# AMU-S02-V00-PSU3V3.net
KiCad netlist of a schematic drawn in Altium Designer
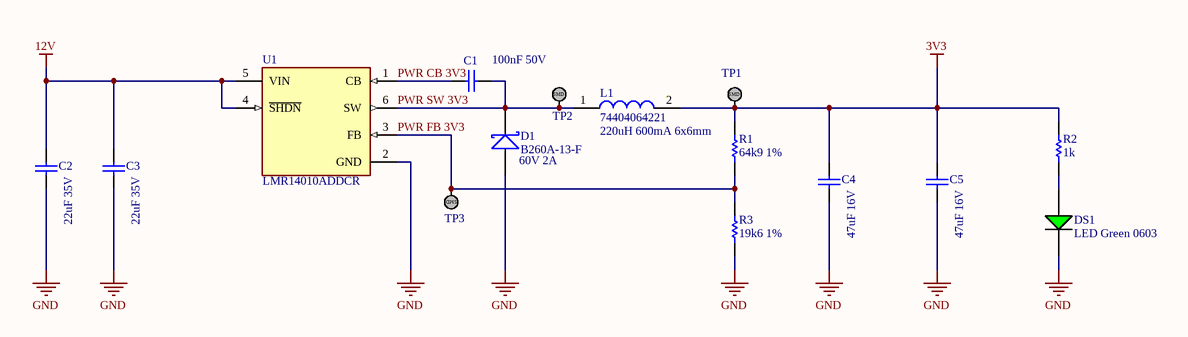
[diagram p0: AMU-S02-V00-PSU3V3.SchDoc]

(export (version "E")
  (design (tool "Eeschema 10.0.6"))
  (components
    (comp (ref "C1")
      (value "100nF 50V")
      (footprint "Cap_Ceramic_0603")
      (description "Capacitor, Ceramic, SMD, 100nF, 50V, 5%, X7R, 0603")
      (libsource (lib "StandardCapacitors") (part "100nF 50V 5% X7R 0603"))
    )
    (comp (ref "C2")
      (value "22uF 35V")
      (footprint "Cap_Ceramic_1206")
      (description "22µF ±20% 35V Ceramic Capacitor X5R 1206 (3216 Metric)")
      (libsource (lib "StandardCapacitors") (part "22uF 35V 20% X5R 1206"))
    )
    (comp (ref "C3")
      (value "22uF 35V")
      (footprint "Cap_Ceramic_1206")
      (description "22µF ±20% 35V Ceramic Capacitor X5R 1206 (3216 Metric)")
      (libsource (lib "StandardCapacitors") (part "22uF 35V 20% X5R 1206"))
    )
    (comp (ref "C4")
      (value "47uF 16V")
      (footprint "Cap_Ceramic_0603")
      (description "Capacitor, Ceramic, SMD, 47uF, 16V, 5%, X7R, 1210")
      (libsource (lib "StandardCapacitors") (part "47uF 16V 10% X7R 1210"))
    )
    (comp (ref "C5")
      (value "47uF 16V")
      (footprint "Cap_Ceramic_0603")
      (description "Capacitor, Ceramic, SMD, 47uF, 16V, 5%, X7R, 1210")
      (libsource (lib "StandardCapacitors") (part "47uF 16V 10% X7R 1210"))
    )
    (comp (ref "D1")
      (value "B260A-13-F")
      (footprint "SMA")
      (description "Diode, Schottky Barrier Rectifier, 60 V, 2 A, B260A-13-F")
      (libsource (lib "QUTMS_DiodeLibrary") (part "B260A-13-F"))
    )
    (comp (ref "DS1")
      (value "LED Green 0603")
      (footprint "LED GREEN 0603")
      (libsource (lib "QUTMS_LEDLibrary") (part "LED Green 0603"))
    )
    (comp (ref "L1")
      (value "74404064221")
      (footprint "Inductor_6x6mm")
      (description "FIXED IND 220UH 660MA 850 MOHM")
      (libsource (lib "QUTMS_InductorLibrary") (part "74404064221"))
    )
    (comp (ref "R1")
      (value "64k9 1%")
      (footprint "Res_ThinFilm_0603")
      (description "Resistor, SMD, 64k9, 0.1W, 5%, 0603")
      (libsource (lib "StandardResistors") (part "64k9 1% 0603"))
    )
    (comp (ref "R2")
      (value "1k")
      (footprint "Res_ThinFilm_0603")
      (description "Resistor, SMD, 1k, 0.1W, 5%, 0603")
      (libsource (lib "StandardResistors") (part "1k 5% 0603"))
    )
    (comp (ref "R3")
      (value "19k6 1%")
      (footprint "Res_ThinFilm_0603")
      (description "Resistor, SMD, 19k6, 0.1W, 5%, 0603")
      (libsource (lib "StandardResistors") (part "19k6 1% 0603"))
    )
    (comp (ref "TP1")
      (value "TestPoint_SMD")
      (footprint "TestPointSMD")
      (libsource (lib "StandardTest") (part "TestPoint_SMD"))
    )
    (comp (ref "TP2")
      (value "TestPoint_SMD")
      (footprint "TestPointSMD")
      (libsource (lib "StandardTest") (part "TestPoint_SMD"))
    )
    (comp (ref "TP3")
      (value "TestPoint_SMD")
      (footprint "TestPointSMD")
      (libsource (lib "StandardTest") (part "TestPoint_SMD"))
    )
    (comp (ref "U1")
      (value "LMR14010ADDCR")
      (footprint "FP-DDC0006A-MFG")
      (description "IC REG BUCK ADJ 1A TSOT23-6")
      (fields
        (field (name "MANUFACTURER") "Texas Instruments")
        (field (name "OCTOPART") "https://octopart.com/lmr14010addcr-texas+instruments-90753290")
      )
      (libsource (lib "Altium Content Vault") (part "248534993f007311ab4e1890f26e637"))
    )
  )
  (nets
    (net (code "1") (name "/PWR CB 3V3") (class "Default")
      (node (ref "C1") (pin "1") (pinfunction "1_1") (pintype "passive"))
      (node (ref "U1") (pin "1") (pinfunction "CB_1") (pintype "input"))
    )
    (net (code "2") (name "/PWR FB 3V3") (class "Default")
      (node (ref "R1") (pin "1") (pinfunction "1_1") (pintype "passive"))
      (node (ref "R3") (pin "2") (pinfunction "2_2") (pintype "passive"))
      (node (ref "TP3") (pin "1") (pinfunction "1_1") (pintype "passive"))
      (node (ref "U1") (pin "3") (pinfunction "FB_3") (pintype "input"))
    )
    (net (code "3") (name "/PWR SW 3V3") (class "Default")
      (node (ref "C1") (pin "2") (pinfunction "2_2") (pintype "passive"))
      (node (ref "D1") (pin "K") (pinfunction "K_K") (pintype "passive"))
      (node (ref "L1") (pin "1") (pinfunction "1_1") (pintype "passive"))
      (node (ref "TP2") (pin "1") (pinfunction "1_1") (pintype "passive"))
      (node (ref "U1") (pin "6") (pinfunction "SW_6") (pintype "output"))
    )
    (net (code "4") (name "3V3") (class "Default")
      (node (ref "C4") (pin "2") (pinfunction "2_2") (pintype "passive"))
      (node (ref "C5") (pin "2") (pinfunction "2_2") (pintype "passive"))
      (node (ref "L1") (pin "2") (pinfunction "2_2") (pintype "passive"))
      (node (ref "R1") (pin "2") (pinfunction "2_2") (pintype "passive"))
      (node (ref "R2") (pin "2") (pinfunction "2_2") (pintype "passive"))
      (node (ref "TP1") (pin "1") (pinfunction "1_1") (pintype "passive"))
    )
    (net (code "5") (name "12V") (class "Default")
      (node (ref "C2") (pin "2") (pinfunction "2_2") (pintype "passive"))
      (node (ref "C3") (pin "2") (pinfunction "2_2") (pintype "passive"))
      (node (ref "U1") (pin "4") (pinfunction "~{SHDN}_4") (pintype "input"))
      (node (ref "U1") (pin "5") (pinfunction "VIN_5") (pintype "power_in"))
    )
    (net (code "6") (name "GND") (class "Default")
      (node (ref "C2") (pin "1") (pinfunction "1_1") (pintype "passive"))
      (node (ref "C3") (pin "1") (pinfunction "1_1") (pintype "passive"))
      (node (ref "C4") (pin "1") (pinfunction "1_1") (pintype "passive"))
      (node (ref "C5") (pin "1") (pinfunction "1_1") (pintype "passive"))
      (node (ref "D1") (pin "A") (pinfunction "A_A") (pintype "passive"))
      (node (ref "DS1") (pin "2") (pinfunction "C_2") (pintype "passive"))
      (node (ref "R3") (pin "1") (pinfunction "1_1") (pintype "passive"))
      (node (ref "U1") (pin "2") (pinfunction "GND_2") (pintype "power_in"))
    )
    (net (code "7") (name "Net-(DS1-A)") (class "Default")
      (node (ref "DS1") (pin "1") (pinfunction "A_1") (pintype "passive"))
      (node (ref "R2") (pin "1") (pinfunction "1_1") (pintype "passive"))
    )
  )
)
